# untitled_6.net
KiCad netlist of a schematic drawn in EAGLE
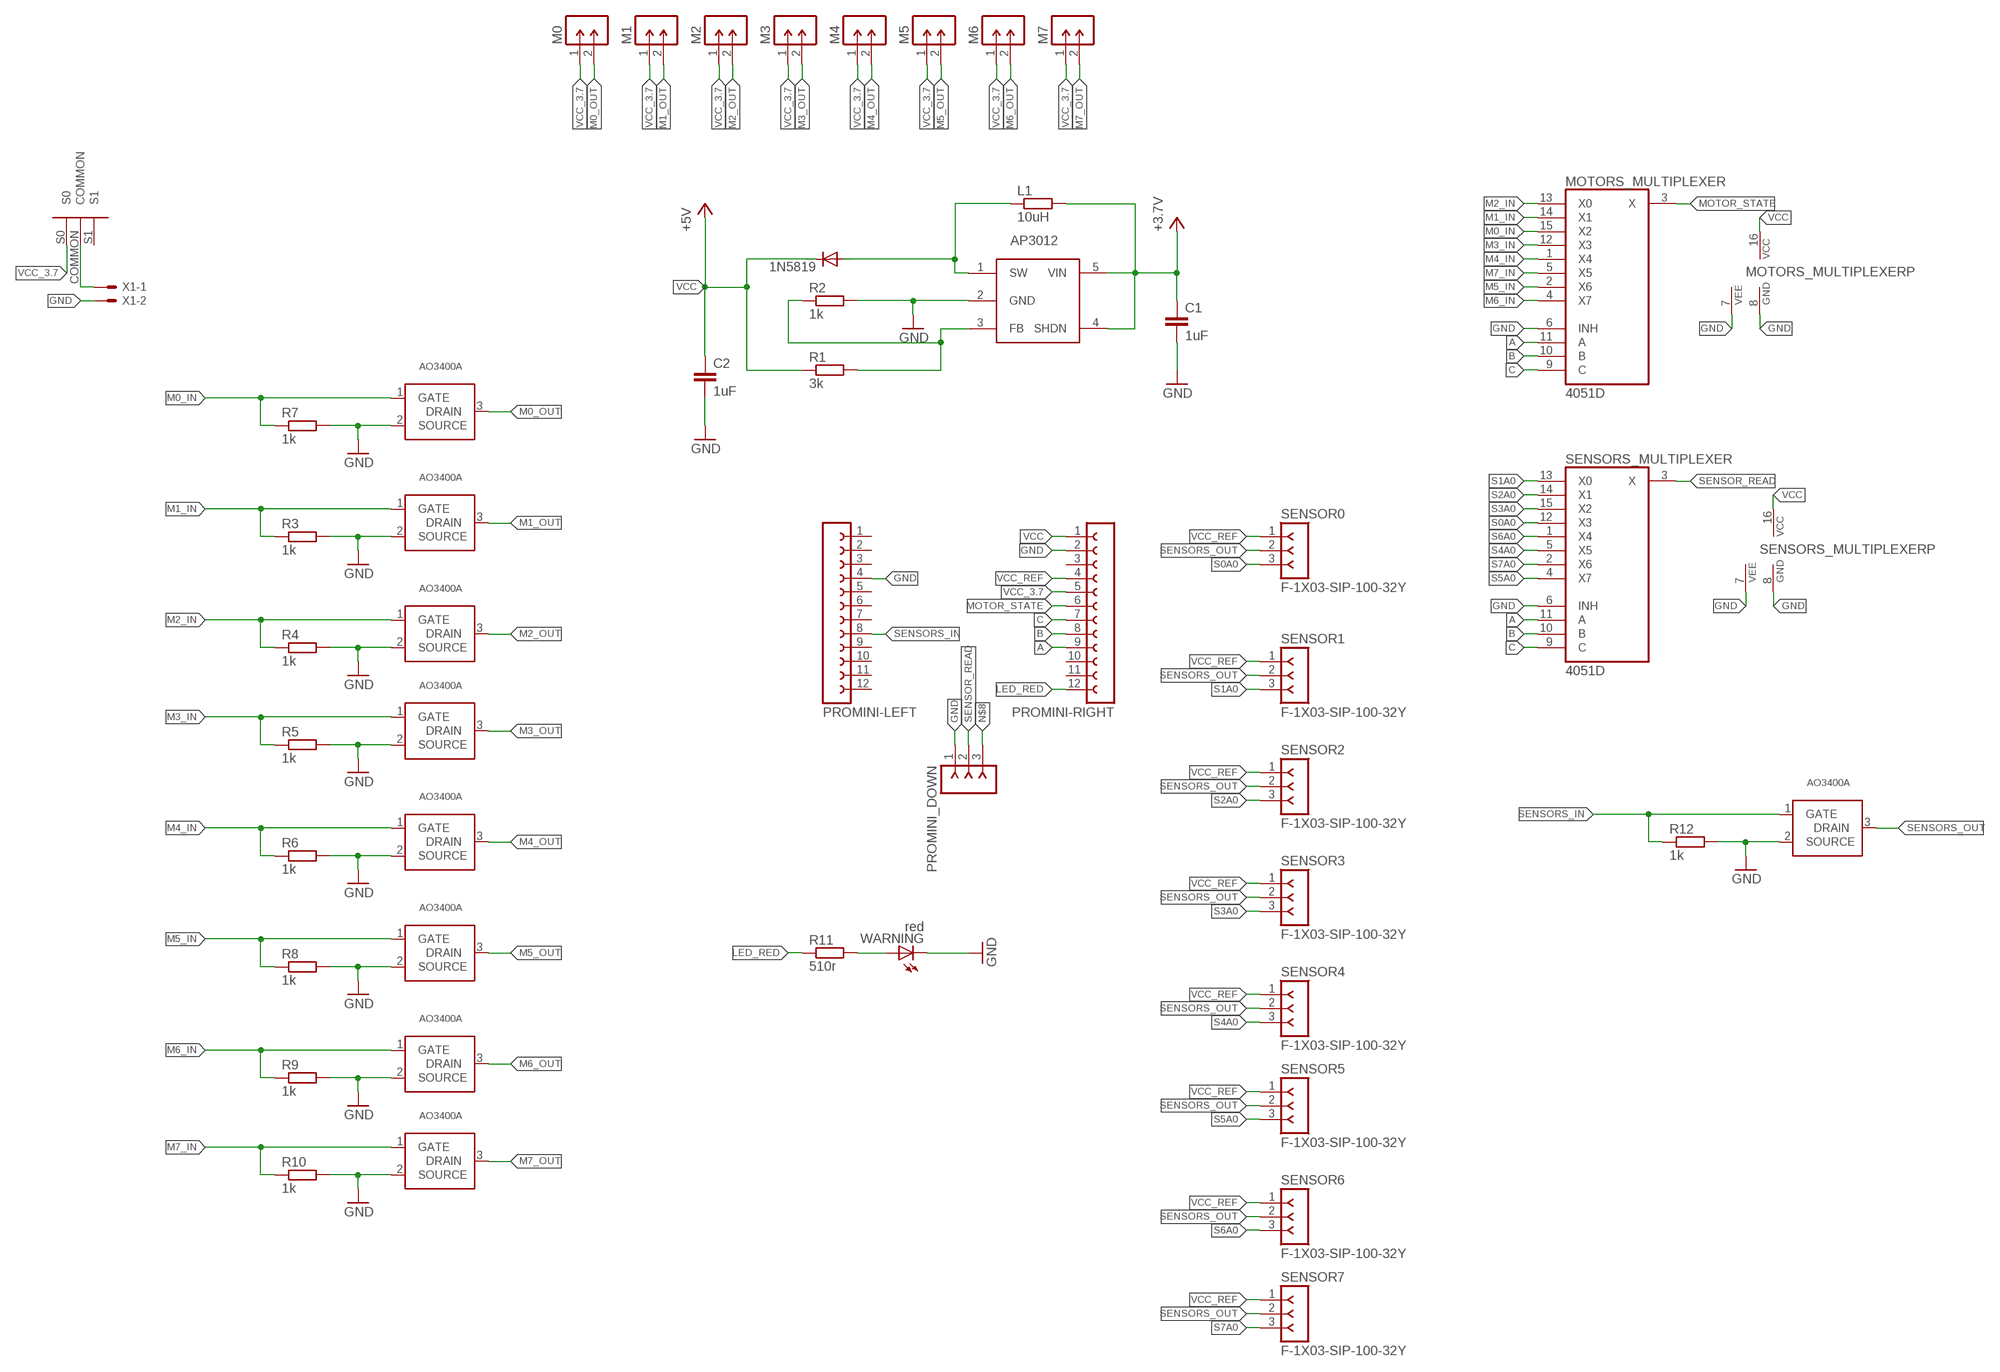
[diagram p0: schematic, sheet 1]

(export (version "E")
  (design (tool "Eeschema 10.0.6"))
  (components
    (comp (ref "1N5819")
      (value "DIODE-DO214AC")
      (footprint "eagle-import:DO214AC")
      (libsource (lib "eagle-import") (part "DIODE-DO214AC"))
    )
    (comp (ref "C1")
      (value "1uF")
      (footprint "eagle-import:C1206")
      (libsource (lib "eagle-import") (part "C-EUC1206"))
    )
    (comp (ref "C2")
      (value "1uF")
      (footprint "eagle-import:C1206")
      (libsource (lib "eagle-import") (part "C-EUC1206"))
    )
    (comp (ref "L1")
      (value "10uH")
      (footprint "eagle-import:R0805")
      (libsource (lib "eagle-import") (part "R-EU_R0805"))
    )
    (comp (ref "M0")
      (value "M-1X02-SIP-100-32Y")
      (footprint "eagle-import:SIP-100-02-32Y")
      (libsource (lib "eagle-import") (part "M-1X02-SIP-100-32Y"))
    )
    (comp (ref "M1")
      (value "M-1X02-SIP-100-32Y")
      (footprint "eagle-import:SIP-100-02-32Y")
      (libsource (lib "eagle-import") (part "M-1X02-SIP-100-32Y"))
    )
    (comp (ref "M2")
      (value "M-1X02-SIP-100-32Y")
      (footprint "eagle-import:SIP-100-02-32Y")
      (libsource (lib "eagle-import") (part "M-1X02-SIP-100-32Y"))
    )
    (comp (ref "M3")
      (value "M-1X02-SIP-100-32Y")
      (footprint "eagle-import:SIP-100-02-32Y")
      (libsource (lib "eagle-import") (part "M-1X02-SIP-100-32Y"))
    )
    (comp (ref "M4")
      (value "M-1X02-SIP-100-32Y")
      (footprint "eagle-import:SIP-100-02-32Y")
      (libsource (lib "eagle-import") (part "M-1X02-SIP-100-32Y"))
    )
    (comp (ref "M5")
      (value "M-1X02-SIP-100-32Y")
      (footprint "eagle-import:SIP-100-02-32Y")
      (libsource (lib "eagle-import") (part "M-1X02-SIP-100-32Y"))
    )
    (comp (ref "M6")
      (value "M-1X02-SIP-100-32Y")
      (footprint "eagle-import:SIP-100-02-32Y")
      (libsource (lib "eagle-import") (part "M-1X02-SIP-100-32Y"))
    )
    (comp (ref "M7")
      (value "M-1X02-SIP-100-32Y")
      (footprint "eagle-import:SIP-100-02-32Y")
      (libsource (lib "eagle-import") (part "M-1X02-SIP-100-32Y"))
    )
    (comp (ref "MOSFET0")
      (value "AO3400A")
      (footprint "eagle-import:SOT-23")
      (libsource (lib "eagle-import") (part "AO3400A"))
    )
    (comp (ref "MOSFET1")
      (value "AO3400A")
      (footprint "eagle-import:SOT-23")
      (libsource (lib "eagle-import") (part "AO3400A"))
    )
    (comp (ref "MOSFET2")
      (value "AO3400A")
      (footprint "eagle-import:SOT-23")
      (libsource (lib "eagle-import") (part "AO3400A"))
    )
    (comp (ref "MOSFET3")
      (value "AO3400A")
      (footprint "eagle-import:SOT-23")
      (libsource (lib "eagle-import") (part "AO3400A"))
    )
    (comp (ref "MOSFET4")
      (value "AO3400A")
      (footprint "eagle-import:SOT-23")
      (libsource (lib "eagle-import") (part "AO3400A"))
    )
    (comp (ref "MOSFET5")
      (value "AO3400A")
      (footprint "eagle-import:SOT-23")
      (libsource (lib "eagle-import") (part "AO3400A"))
    )
    (comp (ref "MOSFET6")
      (value "AO3400A")
      (footprint "eagle-import:SOT-23")
      (libsource (lib "eagle-import") (part "AO3400A"))
    )
    (comp (ref "MOSFET7")
      (value "AO3400A")
      (footprint "eagle-import:SOT-23")
      (libsource (lib "eagle-import") (part "AO3400A"))
    )
    (comp (ref "MOSFET8")
      (value "AO3400A")
      (footprint "eagle-import:SOT-23")
      (libsource (lib "eagle-import") (part "AO3400A"))
    )
    (comp (ref "MOTORS_MULTIPLEXER")
      (value "4051D")
      (footprint "eagle-import:SO16")
      (libsource (lib "eagle-import") (part "4051D"))
    )
    (comp (ref "PROMINI-LEFT")
      (value "FE12-1")
      (footprint "eagle-import:FE12")
      (libsource (lib "eagle-import") (part "FE12-1"))
    )
    (comp (ref "PROMINI-RIGHT")
      (value "FE12-1")
      (footprint "eagle-import:FE12")
      (libsource (lib "eagle-import") (part "FE12-1"))
    )
    (comp (ref "PROMINI_DOWN")
      (value "F-1X03-SIP-100-32Y")
      (footprint "eagle-import:SIP-100-03-32Y")
      (libsource (lib "eagle-import") (part "F-1X03-SIP-100-32Y"))
    )
    (comp (ref "R1")
      (value "3k")
      (footprint "eagle-import:R1206")
      (libsource (lib "eagle-import") (part "R-EU_R1206"))
    )
    (comp (ref "R2")
      (value "1k")
      (footprint "eagle-import:R1206")
      (libsource (lib "eagle-import") (part "R-EU_R1206"))
    )
    (comp (ref "R3")
      (value "1k")
      (footprint "eagle-import:R1206")
      (libsource (lib "eagle-import") (part "R-EU_R1206"))
    )
    (comp (ref "R4")
      (value "1k")
      (footprint "eagle-import:R1206")
      (libsource (lib "eagle-import") (part "R-EU_R1206"))
    )
    (comp (ref "R5")
      (value "1k")
      (footprint "eagle-import:R1206")
      (libsource (lib "eagle-import") (part "R-EU_R1206"))
    )
    (comp (ref "R6")
      (value "1k")
      (footprint "eagle-import:R1206")
      (libsource (lib "eagle-import") (part "R-EU_R1206"))
    )
    (comp (ref "R7")
      (value "1k")
      (footprint "eagle-import:R1206")
      (libsource (lib "eagle-import") (part "R-EU_R1206"))
    )
    (comp (ref "R8")
      (value "1k")
      (footprint "eagle-import:R1206")
      (libsource (lib "eagle-import") (part "R-EU_R1206"))
    )
    (comp (ref "R9")
      (value "1k")
      (footprint "eagle-import:R1206")
      (libsource (lib "eagle-import") (part "R-EU_R1206"))
    )
    (comp (ref "R10")
      (value "1k")
      (footprint "eagle-import:R1206")
      (libsource (lib "eagle-import") (part "R-EU_R1206"))
    )
    (comp (ref "R11")
      (value "510r")
      (footprint "eagle-import:M0805")
      (libsource (lib "eagle-import") (part "R-EU_M0805"))
    )
    (comp (ref "R12")
      (value "1k")
      (footprint "eagle-import:R1206")
      (libsource (lib "eagle-import") (part "R-EU_R1206"))
    )
    (comp (ref "SENSOR0")
      (value "F-1X03-SIP-100-32Y")
      (footprint "eagle-import:SIP-100-03-32Y")
      (libsource (lib "eagle-import") (part "F-1X03-SIP-100-32Y"))
    )
    (comp (ref "SENSOR1")
      (value "F-1X03-SIP-100-32Y")
      (footprint "eagle-import:SIP-100-03-32Y")
      (libsource (lib "eagle-import") (part "F-1X03-SIP-100-32Y"))
    )
    (comp (ref "SENSOR2")
      (value "F-1X03-SIP-100-32Y")
      (footprint "eagle-import:SIP-100-03-32Y")
      (libsource (lib "eagle-import") (part "F-1X03-SIP-100-32Y"))
    )
    (comp (ref "SENSOR3")
      (value "F-1X03-SIP-100-32Y")
      (footprint "eagle-import:SIP-100-03-32Y")
      (libsource (lib "eagle-import") (part "F-1X03-SIP-100-32Y"))
    )
    (comp (ref "SENSOR4")
      (value "F-1X03-SIP-100-32Y")
      (footprint "eagle-import:SIP-100-03-32Y")
      (libsource (lib "eagle-import") (part "F-1X03-SIP-100-32Y"))
    )
    (comp (ref "SENSOR5")
      (value "F-1X03-SIP-100-32Y")
      (footprint "eagle-import:SIP-100-03-32Y")
      (libsource (lib "eagle-import") (part "F-1X03-SIP-100-32Y"))
    )
    (comp (ref "SENSOR6")
      (value "F-1X03-SIP-100-32Y")
      (footprint "eagle-import:SIP-100-03-32Y")
      (libsource (lib "eagle-import") (part "F-1X03-SIP-100-32Y"))
    )
    (comp (ref "SENSOR7")
      (value "F-1X03-SIP-100-32Y")
      (footprint "eagle-import:SIP-100-03-32Y")
      (libsource (lib "eagle-import") (part "F-1X03-SIP-100-32Y"))
    )
    (comp (ref "SENSORS_MULTIPLEXER")
      (value "4051D")
      (footprint "eagle-import:SO16")
      (libsource (lib "eagle-import") (part "4051D"))
    )
    (comp (ref "U$1")
      (value "AP3012")
      (footprint "eagle-import:SOT-23-5")
      (libsource (lib "eagle-import") (part "AP3012"))
    )
    (comp (ref "U$2")
      (value "SPDT_SLIDE_SWITCH_2_PITCH")
      (footprint "eagle-import:SPDT_SLIDE_SWITCH_2_PITCH")
      (libsource (lib "eagle-import") (part "SPDT_SLIDE_SWITCH_2_PITCH"))
    )
    (comp (ref "WARNING")
      (value "red")
      (footprint "eagle-import:CHIP-LED0805")
      (libsource (lib "eagle-import") (part "LEDCHIP-LED0805"))
    )
    (comp (ref "X1")
      (value "JST-XH-02-PIN-LONG-PAD")
      (footprint "eagle-import:JST-XH-02-PACKAGE-LONG-PAD")
      (libsource (lib "eagle-import") (part "JST-XH-02-PIN-LONG-PAD"))
    )
  )
  (nets
    (net (code "1") (name "A") (class "Default")
      (node (ref "MOTORS_MULTIPLEXER") (pin "11") (pinfunction "A_11") (pintype "input"))
      (node (ref "PROMINI-RIGHT") (pin "9") (pinfunction "9_9") (pintype "passive"))
      (node (ref "SENSORS_MULTIPLEXER") (pin "11") (pinfunction "A_11") (pintype "input"))
    )
    (net (code "2") (name "B") (class "Default")
      (node (ref "MOTORS_MULTIPLEXER") (pin "10") (pinfunction "B_10") (pintype "input"))
      (node (ref "PROMINI-RIGHT") (pin "8") (pinfunction "8_8") (pintype "passive"))
      (node (ref "SENSORS_MULTIPLEXER") (pin "10") (pinfunction "B_10") (pintype "input"))
    )
    (net (code "3") (name "C") (class "Default")
      (node (ref "MOTORS_MULTIPLEXER") (pin "9") (pinfunction "C_9") (pintype "input"))
      (node (ref "PROMINI-RIGHT") (pin "7") (pinfunction "7_7") (pintype "passive"))
      (node (ref "SENSORS_MULTIPLEXER") (pin "9") (pinfunction "C_9") (pintype "input"))
    )
    (net (code "4") (name "GND") (class "Default")
      (node (ref "C1") (pin "2") (pinfunction "2_2") (pintype "passive"))
      (node (ref "C2") (pin "2") (pinfunction "2_2") (pintype "passive"))
      (node (ref "MOSFET0") (pin "2") (pinfunction "SOURCE_2") (pintype "bidirectional"))
      (node (ref "MOSFET1") (pin "2") (pinfunction "SOURCE_2") (pintype "bidirectional"))
      (node (ref "MOSFET2") (pin "2") (pinfunction "SOURCE_2") (pintype "bidirectional"))
      (node (ref "MOSFET3") (pin "2") (pinfunction "SOURCE_2") (pintype "bidirectional"))
      (node (ref "MOSFET4") (pin "2") (pinfunction "SOURCE_2") (pintype "bidirectional"))
      (node (ref "MOSFET5") (pin "2") (pinfunction "SOURCE_2") (pintype "bidirectional"))
      (node (ref "MOSFET6") (pin "2") (pinfunction "SOURCE_2") (pintype "bidirectional"))
      (node (ref "MOSFET7") (pin "2") (pinfunction "SOURCE_2") (pintype "bidirectional"))
      (node (ref "MOSFET8") (pin "2") (pinfunction "SOURCE_2") (pintype "bidirectional"))
      (node (ref "MOTORS_MULTIPLEXER") (pin "6") (pinfunction "INH_6") (pintype "input"))
      (node (ref "MOTORS_MULTIPLEXER") (pin "7") (pinfunction "VEE_7") (pintype "power_in"))
      (node (ref "MOTORS_MULTIPLEXER") (pin "8") (pinfunction "GND_8") (pintype "power_in"))
      (node (ref "PROMINI-LEFT") (pin "4") (pinfunction "4_4") (pintype "passive"))
      (node (ref "PROMINI-RIGHT") (pin "2") (pinfunction "2_2") (pintype "passive"))
      (node (ref "PROMINI_DOWN") (pin "1") (pinfunction "1_1") (pintype "passive"))
      (node (ref "R10") (pin "2") (pinfunction "2_2") (pintype "passive"))
      (node (ref "R12") (pin "2") (pinfunction "2_2") (pintype "passive"))
      (node (ref "R2") (pin "2") (pinfunction "2_2") (pintype "passive"))
      (node (ref "R3") (pin "2") (pinfunction "2_2") (pintype "passive"))
      (node (ref "R4") (pin "2") (pinfunction "2_2") (pintype "passive"))
      (node (ref "R5") (pin "2") (pinfunction "2_2") (pintype "passive"))
      (node (ref "R6") (pin "2") (pinfunction "2_2") (pintype "passive"))
      (node (ref "R7") (pin "2") (pinfunction "2_2") (pintype "passive"))
      (node (ref "R8") (pin "2") (pinfunction "2_2") (pintype "passive"))
      (node (ref "R9") (pin "2") (pinfunction "2_2") (pintype "passive"))
      (node (ref "SENSORS_MULTIPLEXER") (pin "6") (pinfunction "INH_6") (pintype "input"))
      (node (ref "SENSORS_MULTIPLEXER") (pin "7") (pinfunction "VEE_7") (pintype "power_in"))
      (node (ref "SENSORS_MULTIPLEXER") (pin "8") (pinfunction "GND_8") (pintype "power_in"))
      (node (ref "U$1") (pin "2") (pinfunction "GND_2") (pintype "bidirectional"))
      (node (ref "WARNING") (pin "C") (pinfunction "C_C") (pintype "passive"))
      (node (ref "X1") (pin "2") (pinfunction "S_2") (pintype "passive"))
    )
    (net (code "5") (name "LED_RED") (class "Default")
      (node (ref "PROMINI-RIGHT") (pin "12") (pinfunction "12_12") (pintype "passive"))
      (node (ref "R11") (pin "1") (pinfunction "1_1") (pintype "passive"))
    )
    (net (code "6") (name "M0_IN") (class "Default")
      (node (ref "MOSFET0") (pin "1") (pinfunction "GATE_1") (pintype "bidirectional"))
      (node (ref "MOTORS_MULTIPLEXER") (pin "15") (pinfunction "X2_15") (pintype "bidirectional"))
      (node (ref "R7") (pin "1") (pinfunction "1_1") (pintype "passive"))
    )
    (net (code "7") (name "M0_OUT") (class "Default")
      (node (ref "M0") (pin "2") (pinfunction "2_2") (pintype "passive"))
      (node (ref "MOSFET0") (pin "3") (pinfunction "DRAIN_3") (pintype "bidirectional"))
    )
    (net (code "8") (name "M1_IN") (class "Default")
      (node (ref "MOSFET1") (pin "1") (pinfunction "GATE_1") (pintype "bidirectional"))
      (node (ref "MOTORS_MULTIPLEXER") (pin "14") (pinfunction "X1_14") (pintype "bidirectional"))
      (node (ref "R3") (pin "1") (pinfunction "1_1") (pintype "passive"))
    )
    (net (code "9") (name "M1_OUT") (class "Default")
      (node (ref "M1") (pin "2") (pinfunction "2_2") (pintype "passive"))
      (node (ref "MOSFET1") (pin "3") (pinfunction "DRAIN_3") (pintype "bidirectional"))
    )
    (net (code "10") (name "M2_IN") (class "Default")
      (node (ref "MOSFET2") (pin "1") (pinfunction "GATE_1") (pintype "bidirectional"))
      (node (ref "MOTORS_MULTIPLEXER") (pin "13") (pinfunction "X0_13") (pintype "bidirectional"))
      (node (ref "R4") (pin "1") (pinfunction "1_1") (pintype "passive"))
    )
    (net (code "11") (name "M2_OUT") (class "Default")
      (node (ref "M2") (pin "2") (pinfunction "2_2") (pintype "passive"))
      (node (ref "MOSFET2") (pin "3") (pinfunction "DRAIN_3") (pintype "bidirectional"))
    )
    (net (code "12") (name "M3_IN") (class "Default")
      (node (ref "MOSFET3") (pin "1") (pinfunction "GATE_1") (pintype "bidirectional"))
      (node (ref "MOTORS_MULTIPLEXER") (pin "12") (pinfunction "X3_12") (pintype "bidirectional"))
      (node (ref "R5") (pin "1") (pinfunction "1_1") (pintype "passive"))
    )
    (net (code "13") (name "M3_OUT") (class "Default")
      (node (ref "M3") (pin "2") (pinfunction "2_2") (pintype "passive"))
      (node (ref "MOSFET3") (pin "3") (pinfunction "DRAIN_3") (pintype "bidirectional"))
    )
    (net (code "14") (name "M4_IN") (class "Default")
      (node (ref "MOSFET4") (pin "1") (pinfunction "GATE_1") (pintype "bidirectional"))
      (node (ref "MOTORS_MULTIPLEXER") (pin "1") (pinfunction "X4_1") (pintype "bidirectional"))
      (node (ref "R6") (pin "1") (pinfunction "1_1") (pintype "passive"))
    )
    (net (code "15") (name "M4_OUT") (class "Default")
      (node (ref "M4") (pin "2") (pinfunction "2_2") (pintype "passive"))
      (node (ref "MOSFET4") (pin "3") (pinfunction "DRAIN_3") (pintype "bidirectional"))
    )
    (net (code "16") (name "M5_IN") (class "Default")
      (node (ref "MOSFET5") (pin "1") (pinfunction "GATE_1") (pintype "bidirectional"))
      (node (ref "MOTORS_MULTIPLEXER") (pin "2") (pinfunction "X6_2") (pintype "bidirectional"))
      (node (ref "R8") (pin "1") (pinfunction "1_1") (pintype "passive"))
    )
    (net (code "17") (name "M5_OUT") (class "Default")
      (node (ref "M5") (pin "2") (pinfunction "2_2") (pintype "passive"))
      (node (ref "MOSFET5") (pin "3") (pinfunction "DRAIN_3") (pintype "bidirectional"))
    )
    (net (code "18") (name "M6_IN") (class "Default")
      (node (ref "MOSFET6") (pin "1") (pinfunction "GATE_1") (pintype "bidirectional"))
      (node (ref "MOTORS_MULTIPLEXER") (pin "4") (pinfunction "X7_4") (pintype "bidirectional"))
      (node (ref "R9") (pin "1") (pinfunction "1_1") (pintype "passive"))
    )
    (net (code "19") (name "M6_OUT") (class "Default")
      (node (ref "M6") (pin "2") (pinfunction "2_2") (pintype "passive"))
      (node (ref "MOSFET6") (pin "3") (pinfunction "DRAIN_3") (pintype "bidirectional"))
    )
    (net (code "20") (name "M7_IN") (class "Default")
      (node (ref "MOSFET7") (pin "1") (pinfunction "GATE_1") (pintype "bidirectional"))
      (node (ref "MOTORS_MULTIPLEXER") (pin "5") (pinfunction "X5_5") (pintype "bidirectional"))
      (node (ref "R10") (pin "1") (pinfunction "1_1") (pintype "passive"))
    )
    (net (code "21") (name "M7_OUT") (class "Default")
      (node (ref "M7") (pin "2") (pinfunction "2_2") (pintype "passive"))
      (node (ref "MOSFET7") (pin "3") (pinfunction "DRAIN_3") (pintype "bidirectional"))
    )
    (net (code "22") (name "MOTOR_STATE") (class "Default")
      (node (ref "MOTORS_MULTIPLEXER") (pin "3") (pinfunction "X_3") (pintype "bidirectional"))
      (node (ref "PROMINI-RIGHT") (pin "6") (pinfunction "6_6") (pintype "passive"))
    )
    (net (code "23") (name "N$8") (class "Default")
      (node (ref "PROMINI_DOWN") (pin "3") (pinfunction "3_3") (pintype "passive"))
    )
    (net (code "24") (name "Net-(R11-Pad2)") (class "Default")
      (node (ref "R11") (pin "2") (pinfunction "2_2") (pintype "passive"))
      (node (ref "WARNING") (pin "A") (pinfunction "A_A") (pintype "passive"))
    )
    (net (code "25") (name "Net-(U$1-FB)") (class "Default")
      (node (ref "R1") (pin "2") (pinfunction "2_2") (pintype "passive"))
      (node (ref "R2") (pin "1") (pinfunction "1_1") (pintype "passive"))
      (node (ref "U$1") (pin "3") (pinfunction "FB_3") (pintype "bidirectional"))
    )
    (net (code "26") (name "Net-(U$1-SW)") (class "Default")
      (node (ref "1N5819") (pin "A") (pinfunction "A_A") (pintype "passive"))
      (node (ref "L1") (pin "1") (pinfunction "1_1") (pintype "passive"))
      (node (ref "U$1") (pin "1") (pinfunction "SW_1") (pintype "bidirectional"))
    )
    (net (code "27") (name "Net-(X1A-S)") (class "Default")
      (node (ref "U$2") (pin "COMMON") (pinfunction "COMMON_COMMON") (pintype "bidirectional"))
      (node (ref "X1") (pin "1") (pinfunction "S_1") (pintype "passive"))
    )
    (net (code "28") (name "S0A0") (class "Default")
      (node (ref "SENSOR0") (pin "3") (pinfunction "3_3") (pintype "passive"))
      (node (ref "SENSORS_MULTIPLEXER") (pin "12") (pinfunction "X3_12") (pintype "bidirectional"))
    )
    (net (code "29") (name "S1A0") (class "Default")
      (node (ref "SENSOR1") (pin "3") (pinfunction "3_3") (pintype "passive"))
      (node (ref "SENSORS_MULTIPLEXER") (pin "13") (pinfunction "X0_13") (pintype "bidirectional"))
    )
    (net (code "30") (name "S2A0") (class "Default")
      (node (ref "SENSOR2") (pin "3") (pinfunction "3_3") (pintype "passive"))
      (node (ref "SENSORS_MULTIPLEXER") (pin "14") (pinfunction "X1_14") (pintype "bidirectional"))
    )
    (net (code "31") (name "S3A0") (class "Default")
      (node (ref "SENSOR3") (pin "3") (pinfunction "3_3") (pintype "passive"))
      (node (ref "SENSORS_MULTIPLEXER") (pin "15") (pinfunction "X2_15") (pintype "bidirectional"))
    )
    (net (code "32") (name "S4A0") (class "Default")
      (node (ref "SENSOR4") (pin "3") (pinfunction "3_3") (pintype "passive"))
      (node (ref "SENSORS_MULTIPLEXER") (pin "5") (pinfunction "X5_5") (pintype "bidirectional"))
    )
    (net (code "33") (name "S5A0") (class "Default")
      (node (ref "SENSOR5") (pin "3") (pinfunction "3_3") (pintype "passive"))
      (node (ref "SENSORS_MULTIPLEXER") (pin "4") (pinfunction "X7_4") (pintype "bidirectional"))
    )
    (net (code "34") (name "S6A0") (class "Default")
      (node (ref "SENSOR6") (pin "3") (pinfunction "3_3") (pintype "passive"))
      (node (ref "SENSORS_MULTIPLEXER") (pin "1") (pinfunction "X4_1") (pintype "bidirectional"))
    )
    (net (code "35") (name "S7A0") (class "Default")
      (node (ref "SENSOR7") (pin "3") (pinfunction "3_3") (pintype "passive"))
      (node (ref "SENSORS_MULTIPLEXER") (pin "2") (pinfunction "X6_2") (pintype "bidirectional"))
    )
    (net (code "36") (name "SENSORS_IN") (class "Default")
      (node (ref "MOSFET8") (pin "1") (pinfunction "GATE_1") (pintype "bidirectional"))
      (node (ref "PROMINI-LEFT") (pin "8") (pinfunction "8_8") (pintype "passive"))
      (node (ref "R12") (pin "1") (pinfunction "1_1") (pintype "passive"))
    )
    (net (code "37") (name "SENSORS_OUT") (class "Default")
      (node (ref "MOSFET8") (pin "3") (pinfunction "DRAIN_3") (pintype "bidirectional"))
      (node (ref "SENSOR0") (pin "2") (pinfunction "2_2") (pintype "passive"))
      (node (ref "SENSOR1") (pin "2") (pinfunction "2_2") (pintype "passive"))
      (node (ref "SENSOR2") (pin "2") (pinfunction "2_2") (pintype "passive"))
      (node (ref "SENSOR3") (pin "2") (pinfunction "2_2") (pintype "passive"))
      (node (ref "SENSOR4") (pin "2") (pinfunction "2_2") (pintype "passive"))
      (node (ref "SENSOR5") (pin "2") (pinfunction "2_2") (pintype "passive"))
      (node (ref "SENSOR6") (pin "2") (pinfunction "2_2") (pintype "passive"))
      (node (ref "SENSOR7") (pin "2") (pinfunction "2_2") (pintype "passive"))
    )
    (net (code "38") (name "SENSOR_READ") (class "Default")
      (node (ref "PROMINI_DOWN") (pin "2") (pinfunction "2_2") (pintype "passive"))
      (node (ref "SENSORS_MULTIPLEXER") (pin "3") (pinfunction "X_3") (pintype "bidirectional"))
    )
    (net (code "39") (name "VCC") (class "Default")
      (node (ref "1N5819") (pin "C") (pinfunction "C_C") (pintype "passive"))
      (node (ref "C2") (pin "1") (pinfunction "1_1") (pintype "passive"))
      (node (ref "MOTORS_MULTIPLEXER") (pin "16") (pinfunction "VCC_16") (pintype "power_in"))
      (node (ref "PROMINI-RIGHT") (pin "1") (pinfunction "1_1") (pintype "passive"))
      (node (ref "R1") (pin "1") (pinfunction "1_1") (pintype "passive"))
      (node (ref "SENSORS_MULTIPLEXER") (pin "16") (pinfunction "VCC_16") (pintype "power_in"))
    )
    (net (code "40") (name "VCC_3.7") (class "Default")
      (node (ref "C1") (pin "1") (pinfunction "1_1") (pintype "passive"))
      (node (ref "L1") (pin "2") (pinfunction "2_2") (pintype "passive"))
      (node (ref "M0") (pin "1") (pinfunction "1_1") (pintype "passive"))
      (node (ref "M1") (pin "1") (pinfunction "1_1") (pintype "passive"))
      (node (ref "M2") (pin "1") (pinfunction "1_1") (pintype "passive"))
      (node (ref "M3") (pin "1") (pinfunction "1_1") (pintype "passive"))
      (node (ref "M4") (pin "1") (pinfunction "1_1") (pintype "passive"))
      (node (ref "M5") (pin "1") (pinfunction "1_1") (pintype "passive"))
      (node (ref "M6") (pin "1") (pinfunction "1_1") (pintype "passive"))
      (node (ref "M7") (pin "1") (pinfunction "1_1") (pintype "passive"))
      (node (ref "PROMINI-RIGHT") (pin "5") (pinfunction "5_5") (pintype "passive"))
      (node (ref "U$1") (pin "4") (pinfunction "SHDN_4") (pintype "bidirectional"))
      (node (ref "U$1") (pin "5") (pinfunction "VIN_5") (pintype "bidirectional"))
      (node (ref "U$2") (pin "S0") (pinfunction "S0_S0") (pintype "bidirectional"))
    )
    (net (code "41") (name "VCC_REF") (class "Default")
      (node (ref "PROMINI-RIGHT") (pin "4") (pinfunction "4_4") (pintype "passive"))
      (node (ref "SENSOR0") (pin "1") (pinfunction "1_1") (pintype "passive"))
      (node (ref "SENSOR1") (pin "1") (pinfunction "1_1") (pintype "passive"))
      (node (ref "SENSOR2") (pin "1") (pinfunction "1_1") (pintype "passive"))
      (node (ref "SENSOR3") (pin "1") (pinfunction "1_1") (pintype "passive"))
      (node (ref "SENSOR4") (pin "1") (pinfunction "1_1") (pintype "passive"))
      (node (ref "SENSOR5") (pin "1") (pinfunction "1_1") (pintype "passive"))
      (node (ref "SENSOR6") (pin "1") (pinfunction "1_1") (pintype "passive"))
      (node (ref "SENSOR7") (pin "1") (pinfunction "1_1") (pintype "passive"))
    )
    (net (code "42") (name "unconnected-(PROMINI-LEFT-Pad1)") (class "Default")
      (node (ref "PROMINI-LEFT") (pin "1") (pinfunction "1_1") (pintype "passive"))
    )
    (net (code "43") (name "unconnected-(PROMINI-LEFT-Pad2)") (class "Default")
      (node (ref "PROMINI-LEFT") (pin "2") (pinfunction "2_2") (pintype "passive"))
    )
    (net (code "44") (name "unconnected-(PROMINI-LEFT-Pad3)") (class "Default")
      (node (ref "PROMINI-LEFT") (pin "3") (pinfunction "3_3") (pintype "passive"))
    )
    (net (code "45") (name "unconnected-(PROMINI-LEFT-Pad5)") (class "Default")
      (node (ref "PROMINI-LEFT") (pin "5") (pinfunction "5_5") (pintype "passive"))
    )
    (net (code "46") (name "unconnected-(PROMINI-LEFT-Pad6)") (class "Default")
      (node (ref "PROMINI-LEFT") (pin "6") (pinfunction "6_6") (pintype "passive"))
    )
    (net (code "47") (name "unconnected-(PROMINI-LEFT-Pad7)") (class "Default")
      (node (ref "PROMINI-LEFT") (pin "7") (pinfunction "7_7") (pintype "passive"))
    )
    (net (code "48") (name "unconnected-(PROMINI-LEFT-Pad9)") (class "Default")
      (node (ref "PROMINI-LEFT") (pin "9") (pinfunction "9_9") (pintype "passive"))
    )
    (net (code "49") (name "unconnected-(PROMINI-LEFT-Pad10)") (class "Default")
      (node (ref "PROMINI-LEFT") (pin "10") (pinfunction "10_10") (pintype "passive"))
    )
    (net (code "50") (name "unconnected-(PROMINI-LEFT-Pad11)") (class "Default")
      (node (ref "PROMINI-LEFT") (pin "11") (pinfunction "11_11") (pintype "passive"))
    )
    (net (code "51") (name "unconnected-(PROMINI-LEFT-Pad12)") (class "Default")
      (node (ref "PROMINI-LEFT") (pin "12") (pinfunction "12_12") (pintype "passive"))
    )
    (net (code "52") (name "unconnected-(PROMINI-RIGHT-Pad3)") (class "Default")
      (node (ref "PROMINI-RIGHT") (pin "3") (pinfunction "3_3") (pintype "passive"))
    )
    (net (code "53") (name "unconnected-(PROMINI-RIGHT-Pad10)") (class "Default")
      (node (ref "PROMINI-RIGHT") (pin "10") (pinfunction "10_10") (pintype "passive"))
    )
    (net (code "54") (name "unconnected-(PROMINI-RIGHT-Pad11)") (class "Default")
      (node (ref "PROMINI-RIGHT") (pin "11") (pinfunction "11_11") (pintype "passive"))
    )
    (net (code "55") (name "unconnected-(U$2-PadS1)") (class "Default")
      (node (ref "U$2") (pin "S1") (pinfunction "S1_S1") (pintype "bidirectional"))
    )
  )
)
